# OLM-periph-probe_ambientREVB.net
KiCad netlist of a schematic drawn in EAGLE
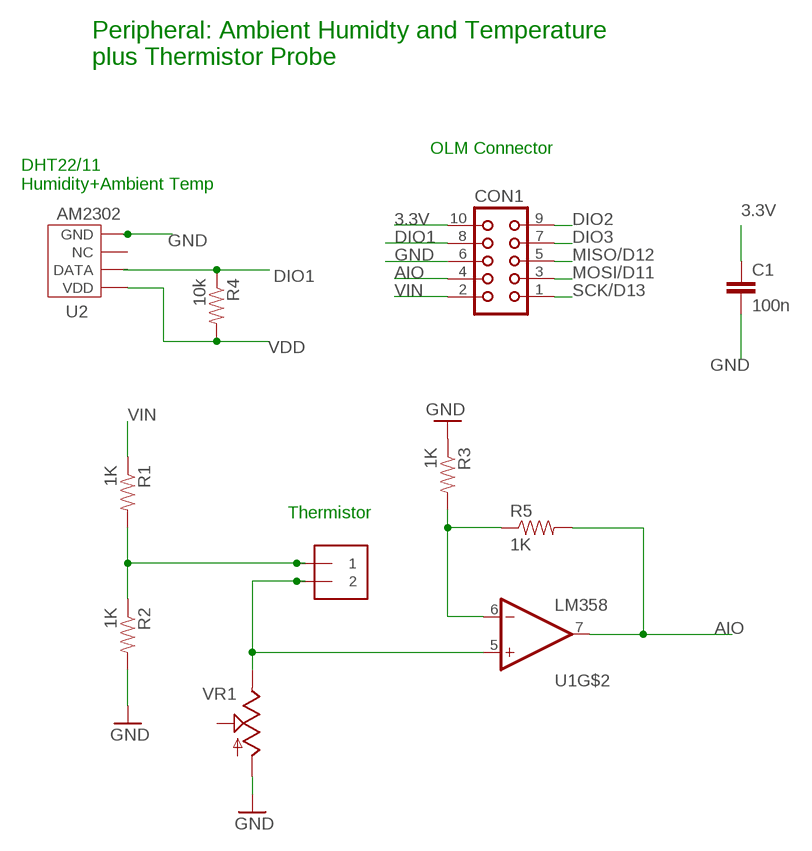
[diagram p0: schematic, sheet 1]

(export (version "E")
  (design (tool "Eeschema 10.0.6"))
  (components
    (comp (ref "C1")
      (value "100n")
      (footprint "eagle-import:C025-024X044")
      (libsource (lib "eagle-import") (part "C-EU025-024X044"))
    )
    (comp (ref "CON1")
      (value "CON10L")
      (footprint "eagle-import:CON10L")
      (libsource (lib "eagle-import") (part "CON10L"))
    )
    (comp (ref "J1")
      (value "1X2-3.5MM")
      (footprint "eagle-import:1X2-3.5MM")
      (libsource (lib "eagle-import") (part "1X2-3.5MM"))
    )
    (comp (ref "R1")
      (value "1K")
      (footprint "eagle-import:AXIAL-0.3")
      (libsource (lib "eagle-import") (part "RESISTORPTH1"))
    )
    (comp (ref "R2")
      (value "1K")
      (footprint "eagle-import:AXIAL-0.3")
      (libsource (lib "eagle-import") (part "RESISTORPTH1"))
    )
    (comp (ref "R3")
      (value "1K")
      (footprint "eagle-import:AXIAL-0.3")
      (libsource (lib "eagle-import") (part "RESISTORPTH1"))
    )
    (comp (ref "R4")
      (value "10k")
      (footprint "eagle-import:AXIAL-0.3")
      (libsource (lib "eagle-import") (part "RESISTORPTH1"))
    )
    (comp (ref "R5")
      (value "1K")
      (footprint "eagle-import:AXIAL-0.3")
      (libsource (lib "eagle-import") (part "RESISTORPTH1"))
    )
    (comp (ref "U1")
      (value "LM358")
      (footprint "eagle-import:DIP08")
      (libsource (lib "eagle-import") (part "LM358"))
    )
    (comp (ref "U2")
      (value "AM2302")
      (footprint "eagle-import:AM2302")
      (libsource (lib "eagle-import") (part "AM2302"))
    )
    (comp (ref "VR1")
      (value "10K")
      (footprint "eagle-import:ALPS_POT")
      (libsource (lib "eagle-import") (part "POT"))
    )
  )
  (nets
    (net (code "1") (name "/3.3V") (class "Default")
      (node (ref "C1") (pin "1") (pinfunction "1_1") (pintype "passive"))
      (node (ref "CON1") (pin "10") (pinfunction "10_10") (pintype "passive"))
    )
    (net (code "2") (name "/AIO") (class "Default")
      (node (ref "CON1") (pin "4") (pinfunction "4_4") (pintype "passive"))
      (node (ref "R5") (pin "P$2") (pinfunction "2_P$2") (pintype "passive"))
      (node (ref "U1") (pin "7") (pinfunction "OUT_7") (pintype "output"))
    )
    (net (code "3") (name "/DIO1") (class "Default")
      (node (ref "CON1") (pin "8") (pinfunction "8_8") (pintype "passive"))
      (node (ref "R4") (pin "P$1") (pinfunction "1_P$1") (pintype "passive"))
      (node (ref "U2") (pin "P$2") (pinfunction "DATA_P$2") (pintype "bidirectional"))
    )
    (net (code "4") (name "/DIO2") (class "Default")
      (node (ref "CON1") (pin "9") (pinfunction "9_9") (pintype "passive"))
    )
    (net (code "5") (name "/DIO3") (class "Default")
      (node (ref "CON1") (pin "7") (pinfunction "7_7") (pintype "passive"))
    )
    (net (code "6") (name "/MISO{slash}D12") (class "Default")
      (node (ref "CON1") (pin "5") (pinfunction "5_5") (pintype "passive"))
    )
    (net (code "7") (name "/MOSI{slash}D11") (class "Default")
      (node (ref "CON1") (pin "3") (pinfunction "3_3") (pintype "passive"))
    )
    (net (code "8") (name "/SCK{slash}D13") (class "Default")
      (node (ref "CON1") (pin "1") (pinfunction "1_1") (pintype "passive"))
    )
    (net (code "9") (name "/VDD") (class "Default")
      (node (ref "R4") (pin "P$2") (pinfunction "2_P$2") (pintype "passive"))
      (node (ref "U2") (pin "P$1") (pinfunction "VDD_P$1") (pintype "power_in"))
    )
    (net (code "10") (name "/VIN") (class "Default")
      (node (ref "CON1") (pin "2") (pinfunction "2_2") (pintype "passive"))
      (node (ref "R1") (pin "P$1") (pinfunction "1_P$1") (pintype "passive"))
    )
    (net (code "11") (name "GND") (class "Default")
      (node (ref "C1") (pin "2") (pinfunction "2_2") (pintype "passive"))
      (node (ref "CON1") (pin "6") (pinfunction "6_6") (pintype "passive"))
      (node (ref "R2") (pin "P$2") (pinfunction "2_P$2") (pintype "passive"))
      (node (ref "R3") (pin "P$1") (pinfunction "1_P$1") (pintype "passive"))
      (node (ref "U2") (pin "P$4") (pinfunction "GND_P$4") (pintype "power_in"))
      (node (ref "VR1") (pin "P$3") (pinfunction "A_P$3") (pintype "passive"))
    )
    (net (code "12") (name "Net-(R1-2)") (class "Default")
      (node (ref "J1") (pin "1") (pinfunction "1_1") (pintype "passive"))
      (node (ref "R1") (pin "P$2") (pinfunction "2_P$2") (pintype "passive"))
      (node (ref "R2") (pin "P$1") (pinfunction "1_P$1") (pintype "passive"))
    )
    (net (code "13") (name "Net-(R3-2)") (class "Default")
      (node (ref "R3") (pin "P$2") (pinfunction "2_P$2") (pintype "passive"))
      (node (ref "R5") (pin "P$1") (pinfunction "1_P$1") (pintype "passive"))
      (node (ref "U1") (pin "6") (pinfunction "-IN_6") (pintype "input"))
    )
    (net (code "14") (name "Net-(U1B-+IN)") (class "Default")
      (node (ref "J1") (pin "2") (pinfunction "2_2") (pintype "passive"))
      (node (ref "U1") (pin "5") (pinfunction "+IN_5") (pintype "input"))
      (node (ref "VR1") (pin "P$1") (pinfunction "E_P$1") (pintype "passive"))
    )
    (net (code "15") (name "unconnected-(U2-NC-PadP$3)") (class "Default")
      (node (ref "U2") (pin "P$3") (pinfunction "NC_P$3") (pintype "no_connect"))
    )
    (net (code "16") (name "unconnected-(VR1-S-PadP$2)") (class "Default")
      (node (ref "VR1") (pin "P$2") (pinfunction "S_P$2") (pintype "passive"))
    )
  )
)
